# echo_in_the_lab.net
KiCad netlist of a schematic drawn in EAGLE
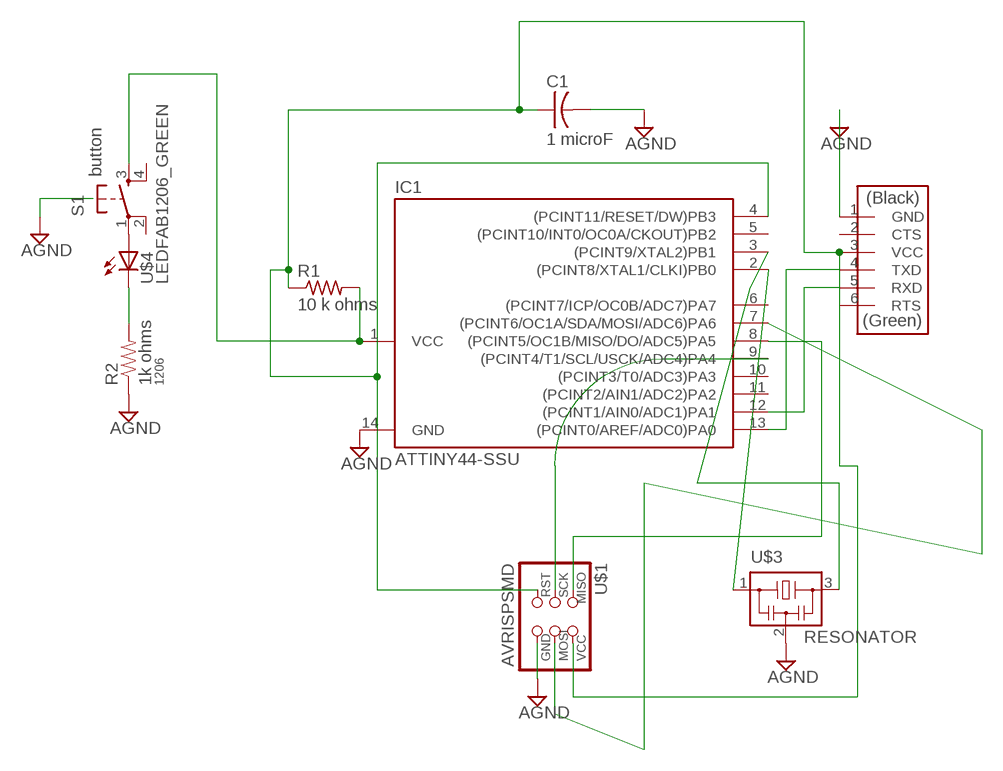
[diagram p0: schematic, sheet 1]

(export (version "E")
  (design (tool "Eeschema 10.0.6"))
  (components
    (comp (ref "C1")
      (value "1 microF")
      (footprint "eagle-import:C1206FAB")
      (libsource (lib "eagle-import") (part "CAP-US1206FAB"))
    )
    (comp (ref "IC1")
      (value "ATTINY44-SSU")
      (footprint "eagle-import:SOIC14")
      (libsource (lib "eagle-import") (part "ATTINY44-SSU"))
    )
    (comp (ref "R1")
      (value "10 k ohms")
      (footprint "eagle-import:R1206W")
      (libsource (lib "eagle-import") (part "RES-US1206W"))
    )
    (comp (ref "R2")
      (value "1k ohms")
      (footprint "eagle-import:1206")
      (libsource (lib "eagle-import") (part "RESISTOR1206"))
    )
    (comp (ref "S1")
      (value "button")
      (footprint "eagle-import:6MM_SWITCH")
      (libsource (lib "eagle-import") (part "6MM_SWITCH6MM_SWITCH"))
    )
    (comp (ref "U$1")
      (value "AVRISPSMD")
      (footprint "eagle-import:2X03SMD")
      (libsource (lib "eagle-import") (part "AVRISPSMD"))
    )
    (comp (ref "U$2")
      (value "FTDI-SMD-HEADER")
      (footprint "eagle-import:1X06SMD")
      (libsource (lib "eagle-import") (part "FTDI-SMD-HEADER"))
    )
    (comp (ref "U$3")
      (value "RESONATOR")
      (footprint "eagle-import:EFOBM")
      (libsource (lib "eagle-import") (part "RESONATOR"))
    )
    (comp (ref "U$4")
      (value "LEDFAB1206_GREEN")
      (footprint "eagle-import:LED1206FAB")
      (libsource (lib "eagle-import") (part "LEDFAB1206"))
    )
  )
  (nets
    (net (code "1") (name "AGND") (class "Default")
      (node (ref "C1") (pin "2") (pinfunction "2_2") (pintype "passive"))
      (node (ref "IC1") (pin "14") (pinfunction "GND_14") (pintype "power_in"))
      (node (ref "R2") (pin "1") (pinfunction "1_1") (pintype "passive"))
      (node (ref "U$1") (pin "6") (pinfunction "GND_6") (pintype "passive"))
      (node (ref "U$2") (pin "1") (pinfunction "GND_1") (pintype "bidirectional"))
      (node (ref "U$3") (pin "2") (pinfunction "2_2") (pintype "passive"))
    )
    (net (code "2") (name "Net-(IC1-(PCINT0{slash}AREF{slash}ADC0)PA0)") (class "Default")
      (node (ref "IC1") (pin "13") (pinfunction "(PCINT0/AREF/ADC0)PA0_13") (pintype "bidirectional"))
      (node (ref "U$2") (pin "4") (pinfunction "TXD_4") (pintype "bidirectional"))
    )
    (net (code "3") (name "Net-(IC1-(PCINT1{slash}AIN0{slash}ADC1)PA1)") (class "Default")
      (node (ref "IC1") (pin "12") (pinfunction "(PCINT1/AIN0/ADC1)PA1_12") (pintype "bidirectional"))
      (node (ref "U$2") (pin "5") (pinfunction "RXD_5") (pintype "bidirectional"))
    )
    (net (code "4") (name "Net-(IC1-(PCINT4{slash}T1{slash}SCL{slash}USCK{slash}ADC4)PA4)") (class "Default")
      (node (ref "IC1") (pin "9") (pinfunction "(PCINT4/T1/SCL/USCK/ADC4)PA4_9") (pintype "bidirectional"))
      (node (ref "U$1") (pin "3") (pinfunction "SCK_3") (pintype "passive"))
    )
    (net (code "5") (name "Net-(IC1-(PCINT5{slash}OC1B{slash}MISO{slash}DO{slash}ADC5)PA5)") (class "Default")
      (node (ref "IC1") (pin "8") (pinfunction "(PCINT5/OC1B/MISO/DO/ADC5)PA5_8") (pintype "bidirectional"))
      (node (ref "U$1") (pin "1") (pinfunction "MISO_1") (pintype "passive"))
    )
    (net (code "6") (name "Net-(IC1-(PCINT6{slash}OC1A{slash}SDA{slash}MOSI{slash}ADC6)PA6)") (class "Default")
      (node (ref "IC1") (pin "7") (pinfunction "(PCINT6/OC1A/SDA/MOSI/ADC6)PA6_7") (pintype "bidirectional"))
      (node (ref "U$1") (pin "4") (pinfunction "MOSI_4") (pintype "passive"))
    )
    (net (code "7") (name "Net-(IC1-(PCINT8{slash}XTAL1{slash}CLKI)PB0)") (class "Default")
      (node (ref "IC1") (pin "2") (pinfunction "(PCINT8/XTAL1/CLKI)PB0_2") (pintype "bidirectional"))
      (node (ref "U$3") (pin "1") (pinfunction "1_1") (pintype "passive"))
    )
    (net (code "8") (name "Net-(IC1-(PCINT9{slash}XTAL2)PB1)") (class "Default")
      (node (ref "IC1") (pin "3") (pinfunction "(PCINT9/XTAL2)PB1_3") (pintype "bidirectional"))
      (node (ref "U$3") (pin "3") (pinfunction "3_3") (pintype "passive"))
    )
    (net (code "9") (name "Net-(IC1-(PCINT11{slash}RESET{slash}DW)PB3)") (class "Default")
      (node (ref "C1") (pin "1") (pinfunction "1_1") (pintype "passive"))
      (node (ref "IC1") (pin "4") (pinfunction "(PCINT11/RESET/DW)PB3_4") (pintype "bidirectional"))
      (node (ref "R1") (pin "1") (pinfunction "1_1") (pintype "passive"))
      (node (ref "U$1") (pin "2") (pinfunction "VCC_2") (pintype "passive"))
      (node (ref "U$1") (pin "5") (pinfunction "RST_5") (pintype "passive"))
      (node (ref "U$2") (pin "3") (pinfunction "VCC_3") (pintype "bidirectional"))
      (node (ref "U$2") (pin "6") (pinfunction "RTS_6") (pintype "bidirectional"))
    )
    (net (code "10") (name "Net-(IC1-VCC)") (class "Default")
      (node (ref "IC1") (pin "1") (pinfunction "VCC_1") (pintype "power_in"))
      (node (ref "R1") (pin "2") (pinfunction "2_2") (pintype "passive"))
      (node (ref "S1") (pin "3") (pinfunction "S_3") (pintype "passive"))
    )
    (net (code "11") (name "Net-(S1-P)") (class "Default")
      (node (ref "S1") (pin "1") (pinfunction "P_1") (pintype "passive"))
      (node (ref "U$4") (pin "1") (pinfunction "A_1") (pintype "passive"))
    )
    (net (code "12") (name "Net-(U$4-C)") (class "Default")
      (node (ref "R2") (pin "2") (pinfunction "2_2") (pintype "passive"))
      (node (ref "U$4") (pin "2") (pinfunction "C_2") (pintype "passive"))
    )
    (net (code "13") (name "unconnected-(IC1-(PCINT2{slash}AIN1{slash}ADC2)PA2-Pad11)") (class "Default")
      (node (ref "IC1") (pin "11") (pinfunction "(PCINT2/AIN1/ADC2)PA2_11") (pintype "bidirectional"))
    )
    (net (code "14") (name "unconnected-(IC1-(PCINT3{slash}T0{slash}ADC3)PA3-Pad10)") (class "Default")
      (node (ref "IC1") (pin "10") (pinfunction "(PCINT3/T0/ADC3)PA3_10") (pintype "bidirectional"))
    )
    (net (code "15") (name "unconnected-(IC1-(PCINT7{slash}ICP{slash}OC0B{slash}ADC7)PA7-Pad6)") (class "Default")
      (node (ref "IC1") (pin "6") (pinfunction "(PCINT7/ICP/OC0B/ADC7)PA7_6") (pintype "bidirectional"))
    )
    (net (code "16") (name "unconnected-(IC1-(PCINT10{slash}INT0{slash}OC0A{slash}CKOUT)PB2-Pad5)") (class "Default")
      (node (ref "IC1") (pin "5") (pinfunction "(PCINT10/INT0/OC0A/CKOUT)PB2_5") (pintype "bidirectional"))
    )
    (net (code "17") (name "unconnected-(S1-P1-Pad2)") (class "Default")
      (node (ref "S1") (pin "2") (pinfunction "P1_2") (pintype "passive"))
    )
    (net (code "18") (name "unconnected-(S1-S1-Pad4)") (class "Default")
      (node (ref "S1") (pin "4") (pinfunction "S1_4") (pintype "passive"))
    )
    (net (code "19") (name "unconnected-(U$2-CTS-Pad2)") (class "Default")
      (node (ref "U$2") (pin "2") (pinfunction "CTS_2") (pintype "bidirectional"))
    )
  )
)
